# -20718.net
KiCad netlist of a schematic drawn in Altium Designer
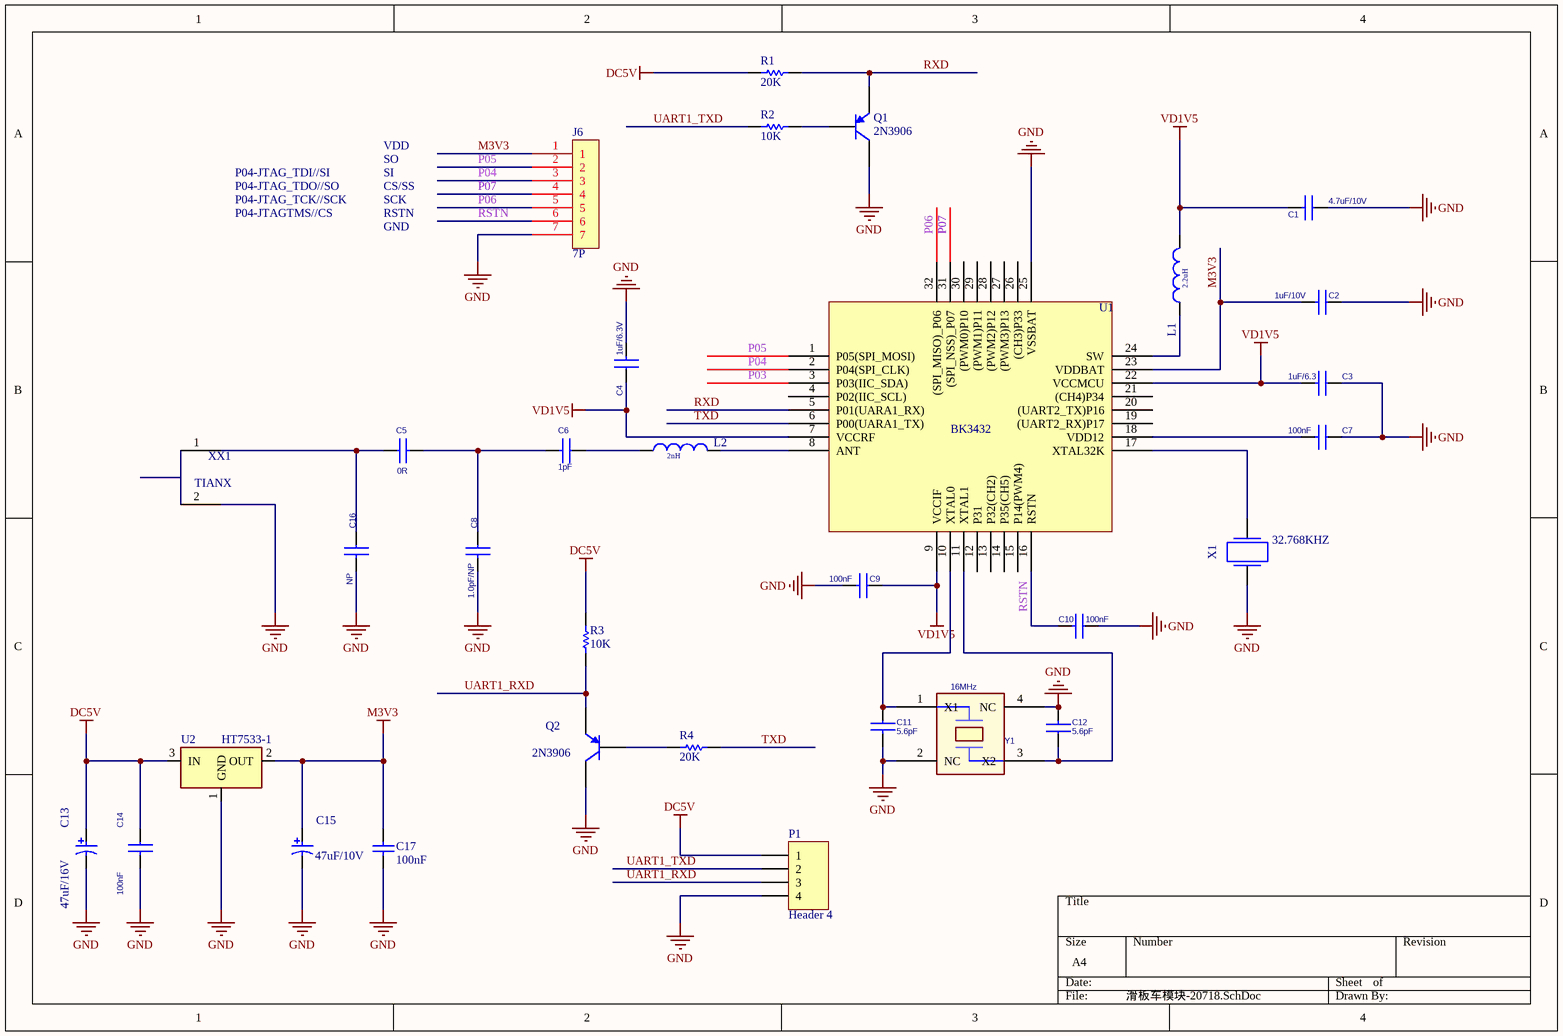
[diagram p0: 滑板车模块-20718.SchDoc]

(export (version "E")
  (design (tool "Eeschema 10.0.6"))
  (components
    (comp (ref "C1") (value "4.7uF/10V") (footprint "LC-0402_C") (libsource (lib "*") (part "CAP0603")))
    (comp (ref "C2") (value "1uF/10V") (footprint "LC-0402_C") (libsource (lib "*") (part "CAP0603")))
    (comp (ref "C3") (value "1uF/6.3") (footprint "LC-0402_C") (libsource (lib "*") (part "CAP0603")))
    (comp (ref "C4") (value "1uF/6.3V") (footprint "LC-0402_C") (libsource (lib "*") (part "CAP0603")))
    (comp (ref "C5") (value "0R") (footprint "LC-0402_C") (libsource (lib "*") (part "CAP0603")))
    (comp (ref "C6") (value "1pF") (footprint "LC-0402_C") (libsource (lib "*") (part "CAP0603")))
    (comp (ref "C7") (value "100nF") (footprint "LC-0402_C") (libsource (lib "*") (part "CAP0603")))
    (comp (ref "C8") (value "1.0pF/NP") (footprint "LC-0402_C") (libsource (lib "*") (part "CAP0603")))
    (comp (ref "C9") (value "100nF") (footprint "LC-0402_C") (libsource (lib "*") (part "CAP0603")))
    (comp (ref "C10") (value "100nF") (footprint "LC-0402_C") (libsource (lib "*") (part "CAP0603")))
    (comp (ref "C11") (value "5.6pF") (footprint "LC-0402_C") (libsource (lib "*") (part "CAP0603")))
    (comp (ref "C12") (value "5.6pF") (footprint "LC-0402_C") (libsource (lib "*") (part "CAP0603")))
    (comp (ref "C13")
      (value "47uF/16V")
      (footprint "LC-0805_C")
      (description "Capacitor, tolerance ±20%")
      (libsource (lib "MySchLib") (part "CAP-P"))
    )
    (comp (ref "C14") (value "100nF") (footprint "LC-0603_C") (libsource (lib "*") (part "CAP NP")))
    (comp (ref "C15")
      (value "47uF/10V")
      (footprint "LC-0805_C")
      (description "Capacitor, tolerance ±20%")
      (libsource (lib "MySchLib") (part "CAP-P"))
    )
    (comp (ref "C16") (value "NP") (footprint "LC-0402_C") (libsource (lib "*") (part "CAP0603")))
    (comp (ref "C17")
      (value "100nF")
      (footprint "LC-0603_C")
      (description "Capacitor, Ceramic")
      (fields (field (name "TOLERANCE") "5 %"))
      (libsource (lib "MyLibrary") (part "CAP-NP"))
    )
    (comp (ref "J6") (value "7P") (footprint "7P-2.0MM") (libsource (lib "保险箱STM32") (part "7P")))
    (comp (ref "L1")
      (value "2.2uH")
      (footprint "LC-0603_L")
      (description "Power Inductor, 4.7uH, 0.7A, 260mR DCR")
      (fields
        (field (name "XMOS PART NUMBER") "E-09-0011")
        (field (name "MANUFACTURER") "Taiyo Yuden")
        (field (name "PART CREATOR") "JG")
        (field (name "APPROVED") "NO")
      )
      (libsource (lib "MySchlib") (part "INDUCTOR"))
    )
    (comp (ref "L2")
      (value "2nH")
      (footprint "LC-0402_L")
      (description "Power Inductor, 4.7uH, 0.7A, 260mR DCR")
      (fields
        (field (name "XMOS PART NUMBER") "E-09-0011")
        (field (name "MANUFACTURER") "Taiyo Yuden")
        (field (name "PART CREATOR") "JG")
        (field (name "APPROVED") "NO")
      )
      (libsource (lib "MySchlib") (part "INDUCTOR"))
    )
    (comp (ref "P1")
      (value "Header 4")
      (footprint "S4B-PH-SM3-TB")
      (description "Header, 4-Pin")
      (fields (field (name "PUBLISHER") "Altium Limited"))
      (libsource (lib "Miscellaneous Connectors") (part "Header 4"))
    )
    (comp (ref "Q1")
      (value "2N3906")
      (footprint "SOT-23-3")
      (description "PNP General Purpose Amplifier")
      (fields (field (name "PUBLISHER") "Altium Limited"))
      (libsource (lib "Miscellaneous Devices") (part "2N3906"))
    )
    (comp (ref "Q2")
      (value "2N3906")
      (footprint "SOT-23-3")
      (description "PNP General Purpose Amplifier")
      (fields (field (name "PUBLISHER") "Altium Limited"))
      (libsource (lib "Miscellaneous Devices") (part "2N3906"))
    )
    (comp (ref "R1")
      (value "20K")
      (footprint "0603R")
      (description "Resistor")
      (fields (field (name "PUBLISHER") "Altium Limited"))
      (libsource (lib "Miscellaneous Devices") (part "Res1"))
    )
    (comp (ref "R2")
      (value "10K")
      (footprint "0603R")
      (description "Resistor")
      (fields (field (name "PUBLISHER") "Altium Limited"))
      (libsource (lib "Miscellaneous Devices") (part "Res1"))
    )
    (comp (ref "R3")
      (value "10K")
      (footprint "0603R")
      (description "Resistor")
      (fields (field (name "PUBLISHER") "Altium Limited"))
      (libsource (lib "Miscellaneous Devices") (part "Res1"))
    )
    (comp (ref "R4")
      (value "20K")
      (footprint "0603R")
      (description "Resistor")
      (fields (field (name "PUBLISHER") "Altium Limited"))
      (libsource (lib "Miscellaneous Devices") (part "Res1"))
    )
    (comp (ref "U1")
      (value "BK3432")
      (footprint "LC-VQFN-32_4x4x04P")
      (libsource (lib "885阿里云PCB_Project1") (part "BK3432"))
    )
    (comp (ref "U2") (value "HT7533-1") (footprint "SOT-23-3L") (libsource (lib "*") (part "XC6206P302M")))
    (comp (ref "X1")
      (value "32.768KHZ")
      (footprint "晶振-9")
      (description "Crystal, 24MHz, HC49/US SMD, Fundamental, 18pF, Tol. ?0ppm, Stab. ?0ppm")
      (fields
        (field (name "XMOS PART NUMBER") "E-07-0030")
        (field (name "MANUFACTURER") "Abracon")
        (field (name "FREQUENCY") "32.768KHZ")
        (field (name "PART CREATOR") "JG")
        (field (name "APPROVED") "NO")
      )
      (libsource (lib "MySchlib") (part "CRYSTAL"))
    )
    (comp (ref "XX1")
      (value "TIANX")
      (footprint "ANT_L_TYPEA_MIRROR")
      (libsource (lib "885阿里云PCB_Project1") (part "TIANX"))
    )
    (comp (ref "Y1") (value "16MHz") (footprint "SMT-3225") (libsource (lib "光学蓝牙") (part "OSCILATOR_0")))
  )
  (nets
    (net (code "1") (name "/P03") (class "Default")
      (node (ref "U1") (pin "3") (pinfunction "P03(IIC_SDA)_3") (pintype "passive"))
    )
    (net (code "2") (name "/P04") (class "Default")
      (node (ref "J6") (pin "3") (pinfunction "3_3") (pintype "passive"))
      (node (ref "U1") (pin "2") (pinfunction "P04(SPI_CLK)_2") (pintype "passive"))
    )
    (net (code "3") (name "/P05") (class "Default")
      (node (ref "J6") (pin "2") (pinfunction "2_2") (pintype "passive"))
      (node (ref "U1") (pin "1") (pinfunction "P05(SPI_MOSI)_1") (pintype "passive"))
    )
    (net (code "4") (name "/P06") (class "Default")
      (node (ref "J6") (pin "5") (pinfunction "5_5") (pintype "passive"))
      (node (ref "U1") (pin "32") (pinfunction "(SPI_MISO)_P06_32") (pintype "passive"))
    )
    (net (code "5") (name "/P07") (class "Default")
      (node (ref "J6") (pin "4") (pinfunction "4_4") (pintype "passive"))
      (node (ref "U1") (pin "31") (pinfunction "(SPI_NSS)_P07_31") (pintype "passive"))
    )
    (net (code "6") (name "/RSTN") (class "Default")
      (node (ref "C10") (pin "2") (pinfunction "2_2") (pintype "passive"))
      (node (ref "J6") (pin "6") (pinfunction "6_6") (pintype "passive"))
      (node (ref "U1") (pin "16") (pinfunction "RSTN_16") (pintype "passive"))
    )
    (net (code "7") (name "/RXD") (class "Default")
      (node (ref "Q1") (pin "2") (pinfunction "E_2") (pintype "passive"))
      (node (ref "R1") (pin "2") (pinfunction "2_2") (pintype "passive"))
      (node (ref "U1") (pin "5") (pinfunction "P01(UARA1_RX)_5") (pintype "passive"))
    )
    (net (code "8") (name "/TXD") (class "Default")
      (node (ref "R4") (pin "1") (pinfunction "1_1") (pintype "passive"))
      (node (ref "U1") (pin "6") (pinfunction "P00(UARA1_TX)_6") (pintype "passive"))
    )
    (net (code "9") (name "/UART1_RXD") (class "Default")
      (node (ref "P1") (pin "3") (pinfunction "3_3") (pintype "passive"))
      (node (ref "Q2") (pin "2") (pinfunction "E_2") (pintype "passive"))
      (node (ref "R3") (pin "2") (pinfunction "2_2") (pintype "passive"))
    )
    (net (code "10") (name "/UART1_TXD") (class "Default")
      (node (ref "P1") (pin "2") (pinfunction "2_2") (pintype "passive"))
      (node (ref "R2") (pin "1") (pinfunction "1_1") (pintype "passive"))
    )
    (net (code "11") (name "DC5V") (class "Default")
      (node (ref "C13") (pin "1") (pinfunction "1_1") (pintype "passive"))
      (node (ref "C14") (pin "1") (pinfunction "1_1") (pintype "passive"))
      (node (ref "P1") (pin "1") (pinfunction "1_1") (pintype "passive"))
      (node (ref "R1") (pin "1") (pinfunction "1_1") (pintype "passive"))
      (node (ref "R3") (pin "1") (pinfunction "1_1") (pintype "passive"))
      (node (ref "U2") (pin "3") (pinfunction "IN_3") (pintype "passive"))
    )
    (net (code "12") (name "GND") (class "Default")
      (node (ref "C1") (pin "1") (pinfunction "1_1") (pintype "passive"))
      (node (ref "C10") (pin "1") (pinfunction "1_1") (pintype "passive"))
      (node (ref "C11") (pin "2") (pinfunction "2_2") (pintype "passive"))
      (node (ref "C12") (pin "2") (pinfunction "2_2") (pintype "passive"))
      (node (ref "C13") (pin "2") (pinfunction "2_2") (pintype "passive"))
      (node (ref "C14") (pin "2") (pinfunction "2_2") (pintype "passive"))
      (node (ref "C15") (pin "2") (pinfunction "2_2") (pintype "passive"))
      (node (ref "C16") (pin "2") (pinfunction "2_2") (pintype "passive"))
      (node (ref "C17") (pin "2") (pinfunction "2_2") (pintype "passive"))
      (node (ref "C2") (pin "1") (pinfunction "1_1") (pintype "passive"))
      (node (ref "C3") (pin "1") (pinfunction "1_1") (pintype "passive"))
      (node (ref "C4") (pin "2") (pinfunction "2_2") (pintype "passive"))
      (node (ref "C7") (pin "1") (pinfunction "1_1") (pintype "passive"))
      (node (ref "C8") (pin "2") (pinfunction "2_2") (pintype "passive"))
      (node (ref "C9") (pin "2") (pinfunction "2_2") (pintype "passive"))
      (node (ref "J6") (pin "7") (pinfunction "7_7") (pintype "passive"))
      (node (ref "P1") (pin "4") (pinfunction "4_4") (pintype "passive"))
      (node (ref "Q1") (pin "3") (pinfunction "C_3") (pintype "passive"))
      (node (ref "Q2") (pin "3") (pinfunction "C_3") (pintype "passive"))
      (node (ref "U1") (pin "25") (pinfunction "VSSBAT_25") (pintype "passive"))
      (node (ref "U2") (pin "1") (pinfunction "GND_1") (pintype "passive"))
      (node (ref "X1") (pin "1") (pinfunction "A_1") (pintype "passive"))
      (node (ref "XX1") (pin "2") (pinfunction "2_2") (pintype "passive"))
      (node (ref "Y1") (pin "2") (pinfunction "NC_2") (pintype "passive"))
      (node (ref "Y1") (pin "4") (pinfunction "NC_4") (pintype "passive"))
    )
    (net (code "13") (name "M3V3") (class "Default")
      (node (ref "C15") (pin "1") (pinfunction "1_1") (pintype "passive"))
      (node (ref "C17") (pin "1") (pinfunction "1_1") (pintype "passive"))
      (node (ref "C2") (pin "2") (pinfunction "2_2") (pintype "passive"))
      (node (ref "J6") (pin "1") (pinfunction "1_1") (pintype "passive"))
      (node (ref "U1") (pin "23") (pinfunction "VDDBAT_23") (pintype "passive"))
      (node (ref "U2") (pin "2") (pinfunction "OUT_2") (pintype "passive"))
    )
    (net (code "14") (name "Net-(C5-Pad2)") (class "Default")
      (node (ref "C5") (pin "2") (pinfunction "2_2") (pintype "passive"))
      (node (ref "C6") (pin "2") (pinfunction "2_2") (pintype "passive"))
      (node (ref "C8") (pin "1") (pinfunction "1_1") (pintype "passive"))
    )
    (net (code "15") (name "Net-(C16-Pad1)") (class "Default")
      (node (ref "C16") (pin "1") (pinfunction "1_1") (pintype "passive"))
      (node (ref "C5") (pin "1") (pinfunction "1_1") (pintype "passive"))
      (node (ref "XX1") (pin "1") (pinfunction "1_1") (pintype "passive"))
    )
    (net (code "16") (name "Net-(L1-P1)") (class "Default")
      (node (ref "L1") (pin "1") (pinfunction "P1_1") (pintype "passive"))
      (node (ref "U1") (pin "24") (pinfunction "SW_24") (pintype "passive"))
    )
    (net (code "17") (name "Net-(L2-P1)") (class "Default")
      (node (ref "C6") (pin "1") (pinfunction "1_1") (pintype "passive"))
      (node (ref "L2") (pin "1") (pinfunction "P1_1") (pintype "passive"))
    )
    (net (code "18") (name "Net-(L2-P2)") (class "Default")
      (node (ref "L2") (pin "2") (pinfunction "P2_2") (pintype "passive"))
      (node (ref "U1") (pin "8") (pinfunction "ANT_8") (pintype "passive"))
    )
    (net (code "19") (name "Net-(Q1-B)") (class "Default")
      (node (ref "Q1") (pin "1") (pinfunction "B_1") (pintype "passive"))
      (node (ref "R2") (pin "2") (pinfunction "2_2") (pintype "passive"))
    )
    (net (code "20") (name "Net-(Q2-B)") (class "Default")
      (node (ref "Q2") (pin "1") (pinfunction "B_1") (pintype "passive"))
      (node (ref "R4") (pin "2") (pinfunction "2_2") (pintype "passive"))
    )
    (net (code "21") (name "Net-(U1-VDD12)") (class "Default")
      (node (ref "C7") (pin "2") (pinfunction "2_2") (pintype "passive"))
      (node (ref "U1") (pin "18") (pinfunction "VDD12_18") (pintype "passive"))
    )
    (net (code "22") (name "Net-(U1-XTAL0)") (class "Default")
      (node (ref "C11") (pin "1") (pinfunction "1_1") (pintype "passive"))
      (node (ref "U1") (pin "10") (pinfunction "XTAL0_10") (pintype "passive"))
      (node (ref "Y1") (pin "1") (pinfunction "X1_1") (pintype "passive"))
    )
    (net (code "23") (name "Net-(U1-XTAL1)") (class "Default")
      (node (ref "C12") (pin "1") (pinfunction "1_1") (pintype "passive"))
      (node (ref "U1") (pin "11") (pinfunction "XTAL1_11") (pintype "passive"))
      (node (ref "Y1") (pin "3") (pinfunction "X2_3") (pintype "passive"))
    )
    (net (code "24") (name "Net-(U1-XTAL32K)") (class "Default")
      (node (ref "U1") (pin "17") (pinfunction "XTAL32K_17") (pintype "passive"))
      (node (ref "X1") (pin "2") (pinfunction "B_2") (pintype "passive"))
    )
    (net (code "25") (name "VD1V5") (class "Default")
      (node (ref "C1") (pin "2") (pinfunction "2_2") (pintype "passive"))
      (node (ref "C3") (pin "2") (pinfunction "2_2") (pintype "passive"))
      (node (ref "C4") (pin "1") (pinfunction "1_1") (pintype "passive"))
      (node (ref "C9") (pin "1") (pinfunction "1_1") (pintype "passive"))
      (node (ref "L1") (pin "2") (pinfunction "P2_2") (pintype "passive"))
      (node (ref "U1") (pin "22") (pinfunction "VCCMCU_22") (pintype "passive"))
      (node (ref "U1") (pin "7") (pinfunction "VCCRF_7") (pintype "passive"))
      (node (ref "U1") (pin "9") (pinfunction "VCCIF_9") (pintype "passive"))
    )
    (net (code "26") (name "unconnected-(U1-(CH3)P33-Pad26)") (class "Default")
      (node (ref "U1") (pin "26") (pinfunction "(CH3)P33_26") (pintype "passive"))
    )
    (net (code "27") (name "unconnected-(U1-(CH4)P34-Pad21)") (class "Default")
      (node (ref "U1") (pin "21") (pinfunction "(CH4)P34_21") (pintype "passive"))
    )
    (net (code "28") (name "unconnected-(U1-(PWM0)P10-Pad30)") (class "Default")
      (node (ref "U1") (pin "30") (pinfunction "(PWM0)P10_30") (pintype "passive"))
    )
    (net (code "29") (name "unconnected-(U1-(PWM1)P11-Pad29)") (class "Default")
      (node (ref "U1") (pin "29") (pinfunction "(PWM1)P11_29") (pintype "passive"))
    )
    (net (code "30") (name "unconnected-(U1-(PWM2)P12-Pad28)") (class "Default")
      (node (ref "U1") (pin "28") (pinfunction "(PWM2)P12_28") (pintype "passive"))
    )
    (net (code "31") (name "unconnected-(U1-(PWM3)P13-Pad27)") (class "Default")
      (node (ref "U1") (pin "27") (pinfunction "(PWM3)P13_27") (pintype "passive"))
    )
    (net (code "32") (name "unconnected-(U1-(UART2_RX)P17-Pad19)") (class "Default")
      (node (ref "U1") (pin "19") (pinfunction "(UART2_RX)P17_19") (pintype "passive"))
    )
    (net (code "33") (name "unconnected-(U1-(UART2_TX)P16-Pad20)") (class "Default")
      (node (ref "U1") (pin "20") (pinfunction "(UART2_TX)P16_20") (pintype "passive"))
    )
    (net (code "34") (name "unconnected-(U1-P02(IIC_SCL)-Pad4)") (class "Default")
      (node (ref "U1") (pin "4") (pinfunction "P02(IIC_SCL)_4") (pintype "passive"))
    )
    (net (code "35") (name "unconnected-(U1-P14(PWM4)-Pad15)") (class "Default")
      (node (ref "U1") (pin "15") (pinfunction "P14(PWM4)_15") (pintype "passive"))
    )
    (net (code "36") (name "unconnected-(U1-P31-Pad12)") (class "Default")
      (node (ref "U1") (pin "12") (pinfunction "P31_12") (pintype "passive"))
    )
    (net (code "37") (name "unconnected-(U1-P32(CH2)-Pad13)") (class "Default")
      (node (ref "U1") (pin "13") (pinfunction "P32(CH2)_13") (pintype "passive"))
    )
    (net (code "38") (name "unconnected-(U1-P35(CH5)-Pad14)") (class "Default")
      (node (ref "U1") (pin "14") (pinfunction "P35(CH5)_14") (pintype "passive"))
    )
  )
)
